# auto-discharge.net
KiCad netlist of a schematic drawn in Altium Designer
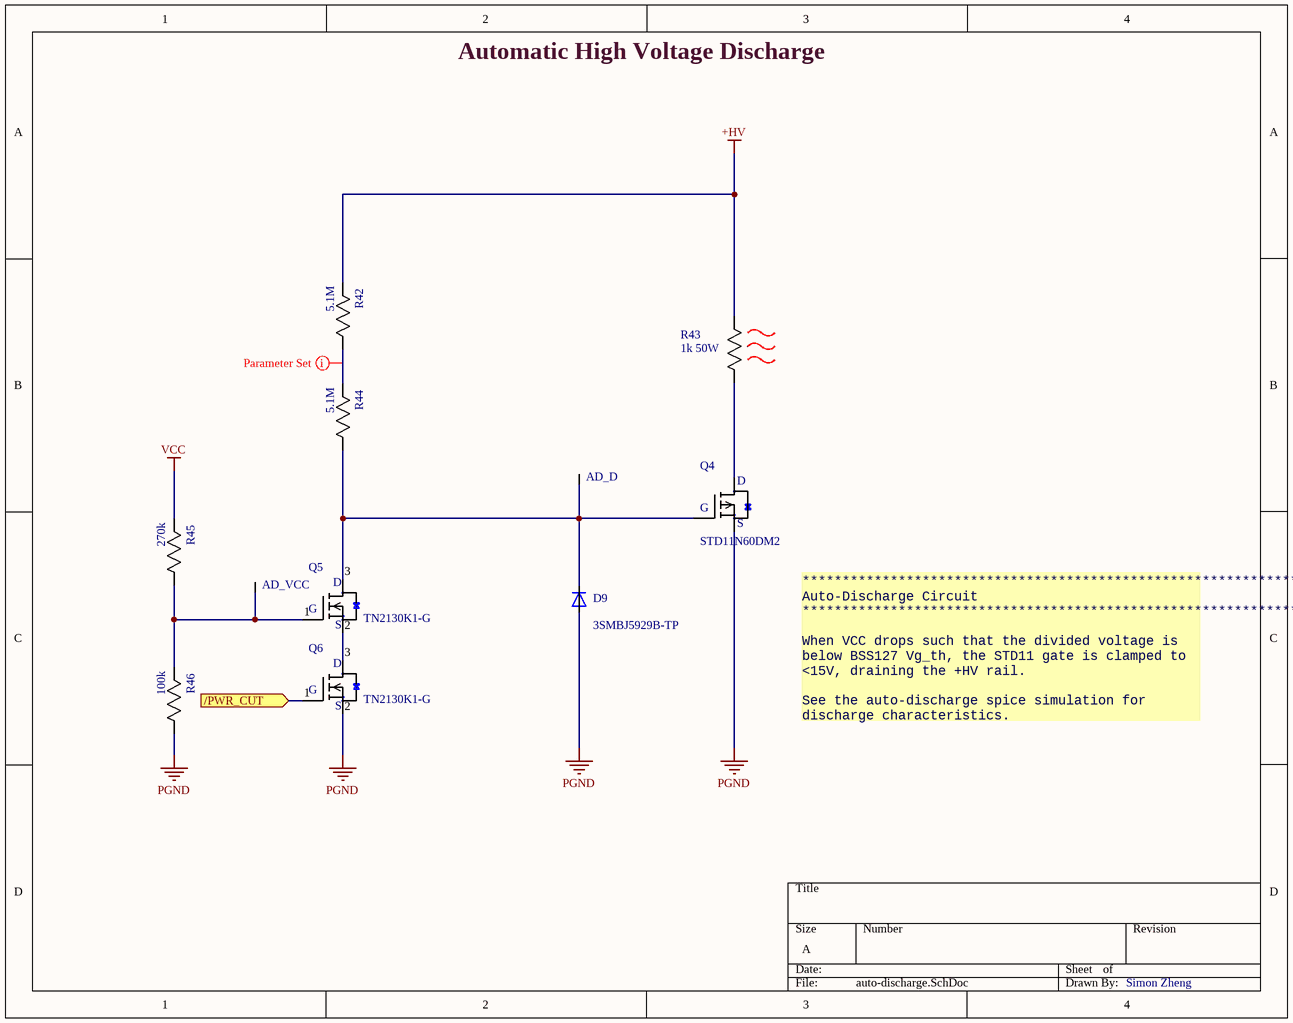
[diagram p0: auto-discharge.SchDoc]

(export (version "E")
  (design (tool "Eeschema 10.0.6"))
  (components
    (comp (ref "AD_D")
      (value "Test Point (Via)")
      (footprint "TP")
      (libsource (lib "IC_Library") (part "Test Point (Via)"))
    )
    (comp (ref "AD_VCC")
      (value "Test Point (Via)")
      (footprint "TP")
      (libsource (lib "IC_Library") (part "Test Point (Via)"))
    )
    (comp (ref "D9")
      (value "3SMBJ5929B-TP")
      (footprint "DO-214AA")
      (description "Diode ZENER 15V 3W")
      (fields (field (name "PART NUMBER") "DIODE ZENER 15V 3W"))
      (libsource (lib "Diode_Library") (part "DIODE ZENER 15V 3W"))
    )
    (comp (ref "Q4")
      (value "STD11N60DM2")
      (footprint "DPAK (TO-252)")
      (fields (field (name "MFG") "STMicroelectronics"))
      (libsource (lib "IC_Library") (part "STD11N60DM2"))
    )
    (comp (ref "Q5")
      (value "TN2130K1-G")
      (footprint "SOT95P237X112-3N")
      (description "N-Channel 300 V 85mA (Tj) 360mW (Tc) Surface Mount TO-236AB (SOT23)")
      (fields
        (field (name "PART NUMBER") "MOSFET N-CH TN2130K1-G")
        (field (name "COPYRIGHT") "Copyright (C) 2021 Ultra Librarian. All rights reserved.")
      )
      (libsource (lib "Transistor_Library") (part "MOSFET N-CH TN2130K1-G"))
    )
    (comp (ref "Q6")
      (value "TN2130K1-G")
      (footprint "SOT95P237X112-3N")
      (description "N-Channel 300 V 85mA (Tj) 360mW (Tc) Surface Mount TO-236AB (SOT23)")
      (fields
        (field (name "PART NUMBER") "MOSFET N-CH TN2130K1-G")
        (field (name "COPYRIGHT") "Copyright (C) 2021 Ultra Librarian. All rights reserved.")
      )
      (libsource (lib "Transistor_Library") (part "MOSFET N-CH TN2130K1-G"))
    )
    (comp (ref "R42")
      (value "5.1M")
      (footprint "0603")
      (description "RES SMD 5.1 MOHM 5% 1/8W 0603")
      (fields (field (name "TOLERANCE") "5%") (field (name "PART NUMBER") "RES 5.1M 1/8W-5%"))
      (libsource (lib "Resistor_Library") (part "RES 5.1M 1/8W-5%"))
    )
    (comp (ref "R43")
      (value "1k 50W")
      (footprint "D2PAK (TO-263)")
      (description "RES SMD 1.5K OHM 1% 50W D2PAK")
      (fields (field (name "TOLERANCE") "1%") (field (name "PART NUMBER") "RES 1.5k 50W"))
      (libsource (lib "Resistor_Library") (part "RES 1.5k 50W"))
    )
    (comp (ref "R44")
      (value "5.1M")
      (footprint "0603")
      (description "RES SMD 5.1 MOHM 5% 1/8W 0603")
      (fields (field (name "TOLERANCE") "5%") (field (name "PART NUMBER") "RES 5.1M 1/8W-5%"))
      (libsource (lib "") (part "RES 5.1M 1/8W-5%_1"))
    )
    (comp (ref "R45")
      (value "270k")
      (footprint "0603")
      (description "RES SMD 270K OHM 5% 1/8W 0603")
      (fields (field (name "TOLERANCE") "5%") (field (name "PART NUMBER") "RES 270k 1/8W"))
      (libsource (lib "Resistor_Library") (part "RES 270k 1/8W"))
    )
    (comp (ref "R46")
      (value "100k")
      (footprint "0603")
      (description "RES SMD 100K OHM 1% 1/8W 0603")
      (fields (field (name "TOLERANCE") "1%") (field (name "PART NUMBER") "RES 100k 1/8W - 1%"))
      (libsource (lib "Resistor_Library") (part "RES 100k 1/8W 1%"))
    )
  )
  (nets
    (net (code "1") (name "+HV") (class "Default")
      (node (ref "R42") (pin "2") (pinfunction "R2_2") (pintype "passive"))
      (node (ref "R43") (pin "2") (pinfunction "R2_2") (pintype "passive"))
    )
    (net (code "2") (name "/{slash}PWR_CUT") (class "Default")
      (node (ref "Q6") (pin "1") (pinfunction "G_1") (pintype "passive"))
    )
    (net (code "3") (name "Net-(Q5-D)") (class "Default")
      (node (ref "AD_D") (pin "1") (pinfunction "1_1") (pintype "passive"))
      (node (ref "D9") (pin "C") (pinfunction "C_C") (pintype "passive"))
      (node (ref "Q4") (pin "G") (pinfunction "G_G") (pintype "passive"))
      (node (ref "Q5") (pin "3") (pinfunction "D_3") (pintype "passive"))
      (node (ref "R44") (pin "1") (pinfunction "R1_1") (pintype "passive"))
    )
    (net (code "4") (name "Net-(Q5-G)") (class "Default")
      (node (ref "AD_VCC") (pin "1") (pinfunction "1_1") (pintype "passive"))
      (node (ref "Q5") (pin "1") (pinfunction "G_1") (pintype "passive"))
      (node (ref "R45") (pin "1") (pinfunction "R1_1") (pintype "passive"))
      (node (ref "R46") (pin "2") (pinfunction "R2_2") (pintype "passive"))
    )
    (net (code "5") (name "Net-(Q5-S)") (class "Default")
      (node (ref "Q5") (pin "2") (pinfunction "S_2") (pintype "passive"))
      (node (ref "Q6") (pin "3") (pinfunction "D_3") (pintype "passive"))
    )
    (net (code "6") (name "Net-(R42-R1)") (class "Default")
      (node (ref "R42") (pin "1") (pinfunction "R1_1") (pintype "passive"))
      (node (ref "R44") (pin "2") (pinfunction "R2_2") (pintype "passive"))
    )
    (net (code "7") (name "Net-(R43-R1)") (class "Default")
      (node (ref "Q4") (pin "D") (pinfunction "D_D") (pintype "passive"))
      (node (ref "R43") (pin "1") (pinfunction "R1_1") (pintype "passive"))
    )
    (net (code "8") (name "PGND") (class "Default")
      (node (ref "D9") (pin "A") (pinfunction "A_A") (pintype "passive"))
      (node (ref "Q4") (pin "S") (pinfunction "S_S") (pintype "passive"))
      (node (ref "Q6") (pin "2") (pinfunction "S_2") (pintype "passive"))
      (node (ref "R46") (pin "1") (pinfunction "R1_1") (pintype "passive"))
    )
    (net (code "9") (name "VCC") (class "Default")
      (node (ref "R45") (pin "2") (pinfunction "R2_2") (pintype "passive"))
    )
    (net (code "10") (name "unconnected-(R43-Pad3)") (class "Default")
      (node (ref "R43") (pin "3") (pinfunction "3_3") (pintype "passive"))
    )
  )
)
